# rapidshark_mark_6_1.net
KiCad netlist of a schematic drawn in EAGLE
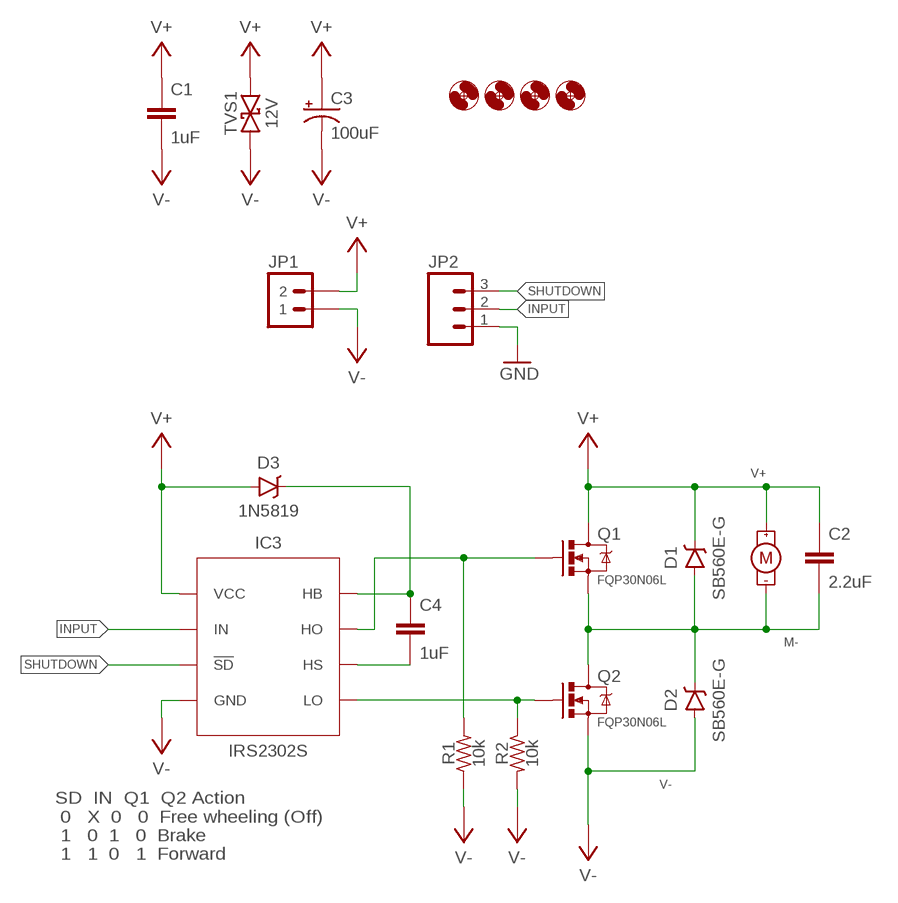
[diagram p0: schematic, sheet 1]

(export (version "E")
  (design (tool "Eeschema 10.0.6"))
  (components
    (comp (ref "C1")
      (value "1uF")
      (footprint "eagle-import:C0805")
      (libsource (lib "eagle-import") (part "CAPACITOR-CERAMICC0805"))
    )
    (comp (ref "C2")
      (value "2.2uF")
      (footprint "eagle-import:C1206")
      (libsource (lib "eagle-import") (part "CAPACITOR-CERAMICC1206"))
    )
    (comp (ref "C3")
      (value "100uF")
      (footprint "eagle-import:E2.5-6-FLAT")
      (libsource (lib "eagle-import") (part "CAPACITOR-POLARIZEDE2.5-6-FLAT"))
    )
    (comp (ref "C4")
      (value "1uF")
      (footprint "eagle-import:C0805")
      (libsource (lib "eagle-import") (part "CAPACITOR-CERAMICC0805"))
    )
    (comp (ref "D1")
      (value "SB560E-G")
      (footprint "eagle-import:DIODE-12.70MM-FAT")
      (libsource (lib "eagle-import") (part "DIODE-SCHOTTKYPTH-12.70-FAT"))
    )
    (comp (ref "D2")
      (value "SB560E-G")
      (footprint "eagle-import:DIODE-12.70MM-FAT")
      (libsource (lib "eagle-import") (part "DIODE-SCHOTTKYPTH-12.70-FAT"))
    )
    (comp (ref "D3")
      (value "1N5819")
      (footprint "eagle-import:SMA-DIODE-SCHOTTKY")
      (libsource (lib "eagle-import") (part "DIODE-SCHOTTKYSMA"))
    )
    (comp (ref "H1")
      (value "HOLE#2")
      (footprint "eagle-import:HOLE-#2")
      (libsource (lib "eagle-import") (part "HOLE#2"))
    )
    (comp (ref "H2")
      (value "HOLE#2")
      (footprint "eagle-import:HOLE-#2")
      (libsource (lib "eagle-import") (part "HOLE#2"))
    )
    (comp (ref "H3")
      (value "HOLE#2")
      (footprint "eagle-import:HOLE-#2")
      (libsource (lib "eagle-import") (part "HOLE#2"))
    )
    (comp (ref "H4")
      (value "HOLE#2")
      (footprint "eagle-import:HOLE-#2")
      (libsource (lib "eagle-import") (part "HOLE#2"))
    )
    (comp (ref "IC3")
      (value "IRS2302S")
      (footprint "eagle-import:SO08")
      (libsource (lib "eagle-import") (part "IRS2302S"))
    )
    (comp (ref "JP1")
      (value "M02PTH4")
      (footprint "eagle-import:1X02_XTRA_BIG")
      (libsource (lib "eagle-import") (part "M02PTH4"))
    )
    (comp (ref "JP2")
      (value "M03JST-PTH")
      (footprint "eagle-import:JST-3-PH-RA-PTH")
      (libsource (lib "eagle-import") (part "M03JST-PTH"))
    )
    (comp (ref "M1")
      (value "MOTORXTRA-BIG")
      (footprint "eagle-import:1X02_XTRA_BIG")
      (libsource (lib "eagle-import") (part "MOTORXTRA-BIG"))
    )
    (comp (ref "Q1")
      (value "FQP30N06L")
      (footprint "eagle-import:TO-220-SIDE-THERM-ALT")
      (libsource (lib "eagle-import") (part "MOSFET-NCHANNELFQP30N06L-THERM"))
    )
    (comp (ref "Q2")
      (value "FQP30N06L")
      (footprint "eagle-import:TO-220-SIDE-THERM-ALT")
      (libsource (lib "eagle-import") (part "MOSFET-NCHANNELFQP30N06L-THERM"))
    )
    (comp (ref "R1")
      (value "10k")
      (footprint "eagle-import:R0805")
      (libsource (lib "eagle-import") (part "RESISTORR0805"))
    )
    (comp (ref "R2")
      (value "10k")
      (footprint "eagle-import:R0805")
      (libsource (lib "eagle-import") (part "RESISTORR0805"))
    )
    (comp (ref "TVS1")
      (value "12V")
      (footprint "eagle-import:DO-41-TVS-BI-10.16MM")
      (libsource (lib "eagle-import") (part "TVSDO-41-10.16MM"))
    )
  )
  (nets
    (net (code "1") (name "/M-") (class "Default")
      (node (ref "C2") (pin "2") (pinfunction "2_2") (pintype "passive"))
      (node (ref "D1") (pin "A") (pinfunction "A_A") (pintype "passive"))
      (node (ref "D2") (pin "K") (pinfunction "C_K") (pintype "passive"))
      (node (ref "M1") (pin "2") (pinfunction "-_2") (pintype "bidirectional"))
      (node (ref "Q1") (pin "3") (pinfunction "S_3") (pintype "passive"))
      (node (ref "Q2") (pin "2") (pinfunction "D_2") (pintype "passive"))
      (node (ref "Q2") (pin "GND@1") (pinfunction "D_GND@1") (pintype "passive"))
      (node (ref "Q2") (pin "GND@10") (pinfunction "D_GND@10") (pintype "passive"))
      (node (ref "Q2") (pin "GND@11") (pinfunction "D_GND@11") (pintype "passive"))
      (node (ref "Q2") (pin "GND@12") (pinfunction "D_GND@12") (pintype "passive"))
      (node (ref "Q2") (pin "GND@13") (pinfunction "D_GND@13") (pintype "passive"))
      (node (ref "Q2") (pin "GND@14") (pinfunction "D_GND@14") (pintype "passive"))
      (node (ref "Q2") (pin "GND@15") (pinfunction "D_GND@15") (pintype "passive"))
      (node (ref "Q2") (pin "GND@16") (pinfunction "D_GND@16") (pintype "passive"))
      (node (ref "Q2") (pin "GND@17") (pinfunction "D_GND@17") (pintype "passive"))
      (node (ref "Q2") (pin "GND@18") (pinfunction "D_GND@18") (pintype "passive"))
      (node (ref "Q2") (pin "GND@19") (pinfunction "D_GND@19") (pintype "passive"))
      (node (ref "Q2") (pin "GND@2") (pinfunction "D_GND@2") (pintype "passive"))
      (node (ref "Q2") (pin "GND@20") (pinfunction "D_GND@20") (pintype "passive"))
      (node (ref "Q2") (pin "GND@21") (pinfunction "D_GND@21") (pintype "passive"))
      (node (ref "Q2") (pin "GND@22") (pinfunction "D_GND@22") (pintype "passive"))
      (node (ref "Q2") (pin "GND@23") (pinfunction "D_GND@23") (pintype "passive"))
      (node (ref "Q2") (pin "GND@24") (pinfunction "D_GND@24") (pintype "passive"))
      (node (ref "Q2") (pin "GND@25") (pinfunction "D_GND@25") (pintype "passive"))
      (node (ref "Q2") (pin "GND@26") (pinfunction "D_GND@26") (pintype "passive"))
      (node (ref "Q2") (pin "GND@27") (pinfunction "D_GND@27") (pintype "passive"))
      (node (ref "Q2") (pin "GND@3") (pinfunction "D_GND@3") (pintype "passive"))
      (node (ref "Q2") (pin "GND@4") (pinfunction "D_GND@4") (pintype "passive"))
      (node (ref "Q2") (pin "GND@5") (pinfunction "D_GND@5") (pintype "passive"))
      (node (ref "Q2") (pin "GND@6") (pinfunction "D_GND@6") (pintype "passive"))
      (node (ref "Q2") (pin "GND@7") (pinfunction "D_GND@7") (pintype "passive"))
      (node (ref "Q2") (pin "GND@8") (pinfunction "D_GND@8") (pintype "passive"))
      (node (ref "Q2") (pin "GND@9") (pinfunction "D_GND@9") (pintype "passive"))
    )
    (net (code "2") (name "GND") (class "Default")
      (node (ref "JP2") (pin "1") (pinfunction "1_1") (pintype "passive"))
    )
    (net (code "3") (name "INPUT") (class "Default")
      (node (ref "IC3") (pin "2") (pinfunction "IN_2") (pintype "passive"))
      (node (ref "JP2") (pin "2") (pinfunction "2_2") (pintype "passive"))
    )
    (net (code "4") (name "Net-(IC3-HB)") (class "Default")
      (node (ref "C4") (pin "1") (pinfunction "1_1") (pintype "passive"))
      (node (ref "D3") (pin "C") (pinfunction "C_C") (pintype "passive"))
      (node (ref "IC3") (pin "8") (pinfunction "HB_8") (pintype "passive"))
    )
    (net (code "5") (name "Net-(IC3-HO)") (class "Default")
      (node (ref "IC3") (pin "7") (pinfunction "HO_7") (pintype "passive"))
      (node (ref "Q1") (pin "1") (pinfunction "G_1") (pintype "passive"))
      (node (ref "R1") (pin "2") (pinfunction "2_2") (pintype "passive"))
    )
    (net (code "6") (name "Net-(IC3-HS)") (class "Default")
      (node (ref "C4") (pin "2") (pinfunction "2_2") (pintype "passive"))
      (node (ref "IC3") (pin "6") (pinfunction "HS_6") (pintype "passive"))
    )
    (net (code "7") (name "Net-(IC3-LO)") (class "Default")
      (node (ref "IC3") (pin "5") (pinfunction "LO_5") (pintype "passive"))
      (node (ref "Q2") (pin "1") (pinfunction "G_1") (pintype "passive"))
      (node (ref "R2") (pin "1") (pinfunction "1_1") (pintype "passive"))
    )
    (net (code "8") (name "SHUTDOWN") (class "Default")
      (node (ref "IC3") (pin "3") (pinfunction "~{SD}_3") (pintype "passive"))
      (node (ref "JP2") (pin "3") (pinfunction "3_3") (pintype "passive"))
    )
    (net (code "9") (name "V+") (class "Default")
      (node (ref "C1") (pin "1") (pinfunction "1_1") (pintype "passive"))
      (node (ref "C2") (pin "1") (pinfunction "1_1") (pintype "passive"))
      (node (ref "C3") (pin "+") (pinfunction "+_+") (pintype "passive"))
      (node (ref "D1") (pin "K") (pinfunction "C_K") (pintype "passive"))
      (node (ref "D3") (pin "A") (pinfunction "A_A") (pintype "passive"))
      (node (ref "IC3") (pin "1") (pinfunction "VCC_1") (pintype "passive"))
      (node (ref "JP1") (pin "2") (pinfunction "2_2") (pintype "passive"))
      (node (ref "M1") (pin "1") (pinfunction "+_1") (pintype "bidirectional"))
      (node (ref "Q1") (pin "2") (pinfunction "D_2") (pintype "passive"))
      (node (ref "Q1") (pin "GND@1") (pinfunction "D_GND@1") (pintype "passive"))
      (node (ref "Q1") (pin "GND@10") (pinfunction "D_GND@10") (pintype "passive"))
      (node (ref "Q1") (pin "GND@11") (pinfunction "D_GND@11") (pintype "passive"))
      (node (ref "Q1") (pin "GND@12") (pinfunction "D_GND@12") (pintype "passive"))
      (node (ref "Q1") (pin "GND@13") (pinfunction "D_GND@13") (pintype "passive"))
      (node (ref "Q1") (pin "GND@14") (pinfunction "D_GND@14") (pintype "passive"))
      (node (ref "Q1") (pin "GND@15") (pinfunction "D_GND@15") (pintype "passive"))
      (node (ref "Q1") (pin "GND@16") (pinfunction "D_GND@16") (pintype "passive"))
      (node (ref "Q1") (pin "GND@17") (pinfunction "D_GND@17") (pintype "passive"))
      (node (ref "Q1") (pin "GND@18") (pinfunction "D_GND@18") (pintype "passive"))
      (node (ref "Q1") (pin "GND@19") (pinfunction "D_GND@19") (pintype "passive"))
      (node (ref "Q1") (pin "GND@2") (pinfunction "D_GND@2") (pintype "passive"))
      (node (ref "Q1") (pin "GND@20") (pinfunction "D_GND@20") (pintype "passive"))
      (node (ref "Q1") (pin "GND@21") (pinfunction "D_GND@21") (pintype "passive"))
      (node (ref "Q1") (pin "GND@22") (pinfunction "D_GND@22") (pintype "passive"))
      (node (ref "Q1") (pin "GND@23") (pinfunction "D_GND@23") (pintype "passive"))
      (node (ref "Q1") (pin "GND@24") (pinfunction "D_GND@24") (pintype "passive"))
      (node (ref "Q1") (pin "GND@25") (pinfunction "D_GND@25") (pintype "passive"))
      (node (ref "Q1") (pin "GND@26") (pinfunction "D_GND@26") (pintype "passive"))
      (node (ref "Q1") (pin "GND@27") (pinfunction "D_GND@27") (pintype "passive"))
      (node (ref "Q1") (pin "GND@3") (pinfunction "D_GND@3") (pintype "passive"))
      (node (ref "Q1") (pin "GND@4") (pinfunction "D_GND@4") (pintype "passive"))
      (node (ref "Q1") (pin "GND@5") (pinfunction "D_GND@5") (pintype "passive"))
      (node (ref "Q1") (pin "GND@6") (pinfunction "D_GND@6") (pintype "passive"))
      (node (ref "Q1") (pin "GND@7") (pinfunction "D_GND@7") (pintype "passive"))
      (node (ref "Q1") (pin "GND@8") (pinfunction "D_GND@8") (pintype "passive"))
      (node (ref "Q1") (pin "GND@9") (pinfunction "D_GND@9") (pintype "passive"))
      (node (ref "TVS1") (pin "P$1") (pinfunction "1_P$1") (pintype "passive"))
    )
    (net (code "10") (name "V-") (class "Default")
      (node (ref "C1") (pin "2") (pinfunction "2_2") (pintype "passive"))
      (node (ref "C3") (pin "-") (pinfunction "-_-") (pintype "passive"))
      (node (ref "D2") (pin "A") (pinfunction "A_A") (pintype "passive"))
      (node (ref "IC3") (pin "4") (pinfunction "GND_4") (pintype "passive"))
      (node (ref "JP1") (pin "1") (pinfunction "1_1") (pintype "passive"))
      (node (ref "Q2") (pin "3") (pinfunction "S_3") (pintype "passive"))
      (node (ref "R1") (pin "1") (pinfunction "1_1") (pintype "passive"))
      (node (ref "R2") (pin "2") (pinfunction "2_2") (pintype "passive"))
      (node (ref "TVS1") (pin "P$2") (pinfunction "2_P$2") (pintype "passive"))
    )
  )
)
